# ir.net
KiCad netlist of a schematic drawn in EAGLE
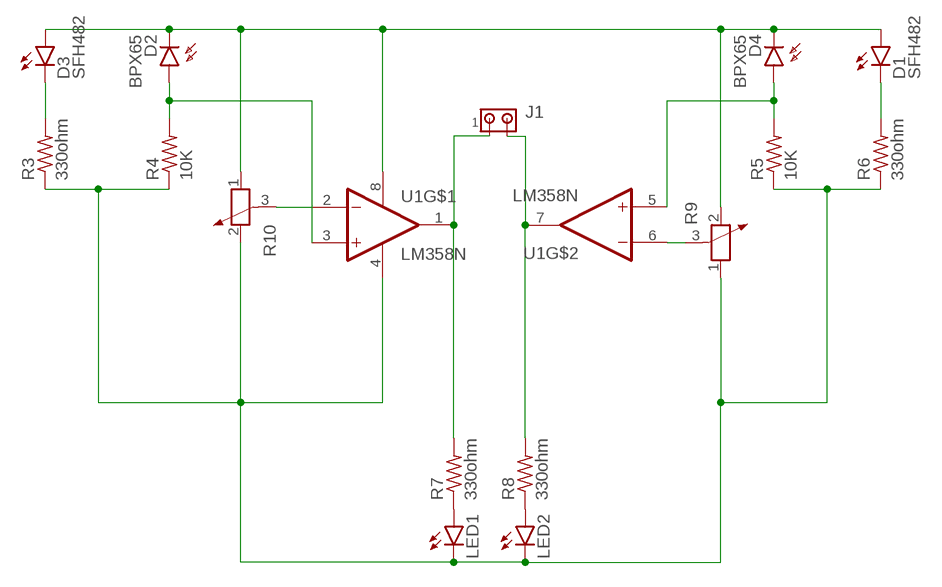
[diagram p0: schematic, sheet 1]

(export (version "E")
  (design (tool "Eeschema 10.0.6"))
  (components
    (comp (ref "D1")
      (value "SFH482")
      (footprint "eagle-import:SFH482")
      (libsource (lib "eagle-import") (part "SFH482"))
    )
    (comp (ref "D2")
      (value "BPX65")
      (footprint "eagle-import:BPX65")
      (fields (field (name "MPN") "BPX65."))
      (libsource (lib "eagle-import") (part "BPX65"))
    )
    (comp (ref "D3")
      (value "SFH482")
      (footprint "eagle-import:SFH482")
      (libsource (lib "eagle-import") (part "SFH482"))
    )
    (comp (ref "D4")
      (value "BPX65")
      (footprint "eagle-import:BPX65")
      (fields (field (name "MPN") "BPX65."))
      (libsource (lib "eagle-import") (part "BPX65"))
    )
    (comp (ref "J1")
      (value "MTA02-100")
      (footprint "eagle-import:10X02MTA")
      (libsource (lib "eagle-import") (part "MTA02-100"))
    )
    (comp (ref "LED1")
      (value "LED3MM")
      (footprint "eagle-import:LED3MM")
      (libsource (lib "eagle-import") (part "LED3MM"))
    )
    (comp (ref "LED2")
      (value "LED3MM")
      (footprint "eagle-import:LED3MM")
      (libsource (lib "eagle-import") (part "LED3MM"))
    )
    (comp (ref "R3")
      (value "330ohm")
      (footprint "eagle-import:0204_5")
      (libsource (lib "eagle-import") (part "R-US_0204/5"))
    )
    (comp (ref "R4")
      (value "10K")
      (footprint "eagle-import:0204_5")
      (libsource (lib "eagle-import") (part "R-US_0204/5"))
    )
    (comp (ref "R5")
      (value "10K")
      (footprint "eagle-import:0204_5")
      (libsource (lib "eagle-import") (part "R-US_0204/5"))
    )
    (comp (ref "R6")
      (value "330ohm")
      (footprint "eagle-import:0204_5")
      (libsource (lib "eagle-import") (part "R-US_0204/5"))
    )
    (comp (ref "R7")
      (value "330ohm")
      (footprint "eagle-import:0204_5")
      (libsource (lib "eagle-import") (part "R-US_0204/5"))
    )
    (comp (ref "R8")
      (value "330ohm")
      (footprint "eagle-import:0204_5")
      (libsource (lib "eagle-import") (part "R-US_0204/5"))
    )
    (comp (ref "R9")
      (value "POTENTIOMETER_PT-10")
      (footprint "eagle-import:PT-10")
      (libsource (lib "eagle-import") (part "POTENTIOMETER_PT-10"))
    )
    (comp (ref "R10")
      (value "POTENTIOMETER_PT-10")
      (footprint "eagle-import:PT-10")
      (libsource (lib "eagle-import") (part "POTENTIOMETER_PT-10"))
    )
    (comp (ref "U1")
      (value "LM358N")
      (footprint "eagle-import:DIP762W46P254L960H508Q8")
      (fields (field (name "MF") "Harris Corporation"))
      (libsource (lib "eagle-import") (part "LM358N"))
    )
  )
  (nets
    (net (code "1") (name "Net-(D1-C)") (class "Default")
      (node (ref "D1") (pin "K") (pinfunction "C_K") (pintype "passive"))
      (node (ref "R6") (pin "2") (pinfunction "2_2") (pintype "passive"))
    )
    (net (code "2") (name "Net-(D2-C)") (class "Default")
      (node (ref "D1") (pin "A") (pinfunction "A_A") (pintype "passive"))
      (node (ref "D2") (pin "K") (pinfunction "C_K") (pintype "passive"))
      (node (ref "D3") (pin "A") (pinfunction "A_A") (pintype "passive"))
      (node (ref "D4") (pin "K") (pinfunction "C_K") (pintype "passive"))
      (node (ref "R10") (pin "1") (pinfunction "1_1") (pintype "passive"))
      (node (ref "R9") (pin "2") (pinfunction "2_2") (pintype "passive"))
      (node (ref "U1") (pin "8") (pinfunction "VCC_8") (pintype "power_in"))
    )
    (net (code "3") (name "Net-(D3-C)") (class "Default")
      (node (ref "D3") (pin "K") (pinfunction "C_K") (pintype "passive"))
      (node (ref "R3") (pin "2") (pinfunction "2_2") (pintype "passive"))
    )
    (net (code "4") (name "Net-(LED1-C)") (class "Default")
      (node (ref "LED1") (pin "K") (pinfunction "C_K") (pintype "passive"))
      (node (ref "LED2") (pin "K") (pinfunction "C_K") (pintype "passive"))
      (node (ref "R10") (pin "2") (pinfunction "2_2") (pintype "passive"))
      (node (ref "R3") (pin "1") (pinfunction "1_1") (pintype "passive"))
      (node (ref "R4") (pin "1") (pinfunction "1_1") (pintype "passive"))
      (node (ref "R5") (pin "1") (pinfunction "1_1") (pintype "passive"))
      (node (ref "R6") (pin "1") (pinfunction "1_1") (pintype "passive"))
      (node (ref "R9") (pin "1") (pinfunction "1_1") (pintype "passive"))
      (node (ref "U1") (pin "4") (pinfunction "GND_4") (pintype "power_in"))
    )
    (net (code "5") (name "Net-(LED1-PadA)") (class "Default")
      (node (ref "LED1") (pin "A") (pinfunction "A_A") (pintype "passive"))
      (node (ref "R7") (pin "1") (pinfunction "1_1") (pintype "passive"))
    )
    (net (code "6") (name "Net-(LED2-PadA)") (class "Default")
      (node (ref "LED2") (pin "A") (pinfunction "A_A") (pintype "passive"))
      (node (ref "R8") (pin "1") (pinfunction "1_1") (pintype "passive"))
    )
    (net (code "7") (name "Net-(U1A-1IN+)") (class "Default")
      (node (ref "D2") (pin "A") (pinfunction "A_A") (pintype "passive"))
      (node (ref "R4") (pin "2") (pinfunction "2_2") (pintype "passive"))
      (node (ref "U1") (pin "3") (pinfunction "1IN+_3") (pintype "input"))
    )
    (net (code "8") (name "Net-(U1A-1IN-)") (class "Default")
      (node (ref "R10") (pin "3") (pinfunction "3_3") (pintype "passive"))
      (node (ref "U1") (pin "2") (pinfunction "1IN-_2") (pintype "input"))
    )
    (net (code "9") (name "Net-(U1A-1OUT)") (class "Default")
      (node (ref "J1") (pin "1") (pinfunction "1_1") (pintype "passive"))
      (node (ref "R7") (pin "2") (pinfunction "2_2") (pintype "passive"))
      (node (ref "U1") (pin "1") (pinfunction "1OUT_1") (pintype "output"))
    )
    (net (code "10") (name "Net-(U1B-2IN+)") (class "Default")
      (node (ref "D4") (pin "A") (pinfunction "A_A") (pintype "passive"))
      (node (ref "R5") (pin "2") (pinfunction "2_2") (pintype "passive"))
      (node (ref "U1") (pin "5") (pinfunction "2IN+_5") (pintype "input"))
    )
    (net (code "11") (name "Net-(U1B-2IN-)") (class "Default")
      (node (ref "R9") (pin "3") (pinfunction "3_3") (pintype "passive"))
      (node (ref "U1") (pin "6") (pinfunction "2IN-_6") (pintype "input"))
    )
    (net (code "12") (name "Net-(U1B-2OUT)") (class "Default")
      (node (ref "J1") (pin "2") (pinfunction "2_2") (pintype "passive"))
      (node (ref "R8") (pin "2") (pinfunction "2_2") (pintype "passive"))
      (node (ref "U1") (pin "7") (pinfunction "2OUT_7") (pintype "output"))
    )
  )
)
